# TP_IHM_BUZZER.net
KiCad netlist of a schematic drawn in Altium Designer
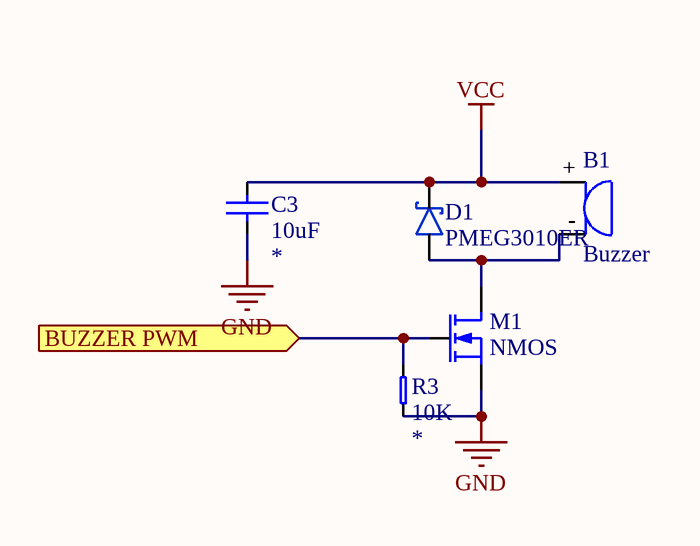
[diagram p0: TP_IHM_BUZZER.SchDoc]

(export (version "E")
  (design (tool "Eeschema 10.0.6"))
  (components
    (comp (ref "B1")
      (value "Buzzer")
      (footprint "SD160709")
      (description "TDK SD160709 Buzzer")
      (libsource (lib "TpGiven") (part "SD160709"))
    )
    (comp (ref "C3")
      (value "10uF")
      (footprint "0603_CAP_LD")
      (description "Ceramic Capacitor")
      (fields (field (name "PACKAGE") "*") (field (name "Comment") "CerCap"))
      (libsource (lib "TpGiven") (part "CerCap"))
    )
    (comp (ref "D1")
      (value "PMEG3010ER")
      (footprint "SOD123W")
      (description "Nexperia 1A low Vf Mega Schottky barrier rectifier")
      (libsource (lib "TpGiven") (part "Schottky_PMEG3010ER"))
    )
    (comp (ref "M1")
      (value "NMOS")
      (footprint "MOSFET-SOT23")
      (description "N MOSFET")
      (libsource (lib "TpGiven") (part "N-MOSFET"))
    )
    (comp (ref "R3")
      (value "10K")
      (footprint "0603_RES_LD")
      (description "Resistor")
      (fields (field (name "PACKAGE") "*"))
      (libsource (lib "TpGiven") (part "Resistor"))
    )
  )
  (nets
    (net (code "1") (name "/BUZZER PWM") (class "Default")
      (node (ref "M1") (pin "G") (pinfunction "G_G") (pintype "passive"))
      (node (ref "R3") (pin "2") (pinfunction "2_2") (pintype "passive"))
    )
    (net (code "2") (name "GND") (class "Default")
      (node (ref "C3") (pin "1") (pinfunction "1_1") (pintype "passive"))
      (node (ref "M1") (pin "S") (pinfunction "S_S") (pintype "passive"))
      (node (ref "R3") (pin "1") (pinfunction "1_1") (pintype "passive"))
    )
    (net (code "3") (name "Net-(D1-1)") (class "Default")
      (node (ref "B1") (pin "-") (pinfunction "-_-") (pintype "passive"))
      (node (ref "D1") (pin "A") (pinfunction "1_A") (pintype "passive"))
      (node (ref "M1") (pin "D") (pinfunction "D_D") (pintype "passive"))
    )
    (net (code "4") (name "VCC") (class "Default")
      (node (ref "B1") (pin "+") (pinfunction "+_+") (pintype "passive"))
      (node (ref "C3") (pin "2") (pinfunction "2_2") (pintype "passive"))
      (node (ref "D1") (pin "K") (pinfunction "2_K") (pintype "passive"))
    )
  )
)
